# EtherGeiger.net
KiCad netlist of a schematic drawn in EAGLE
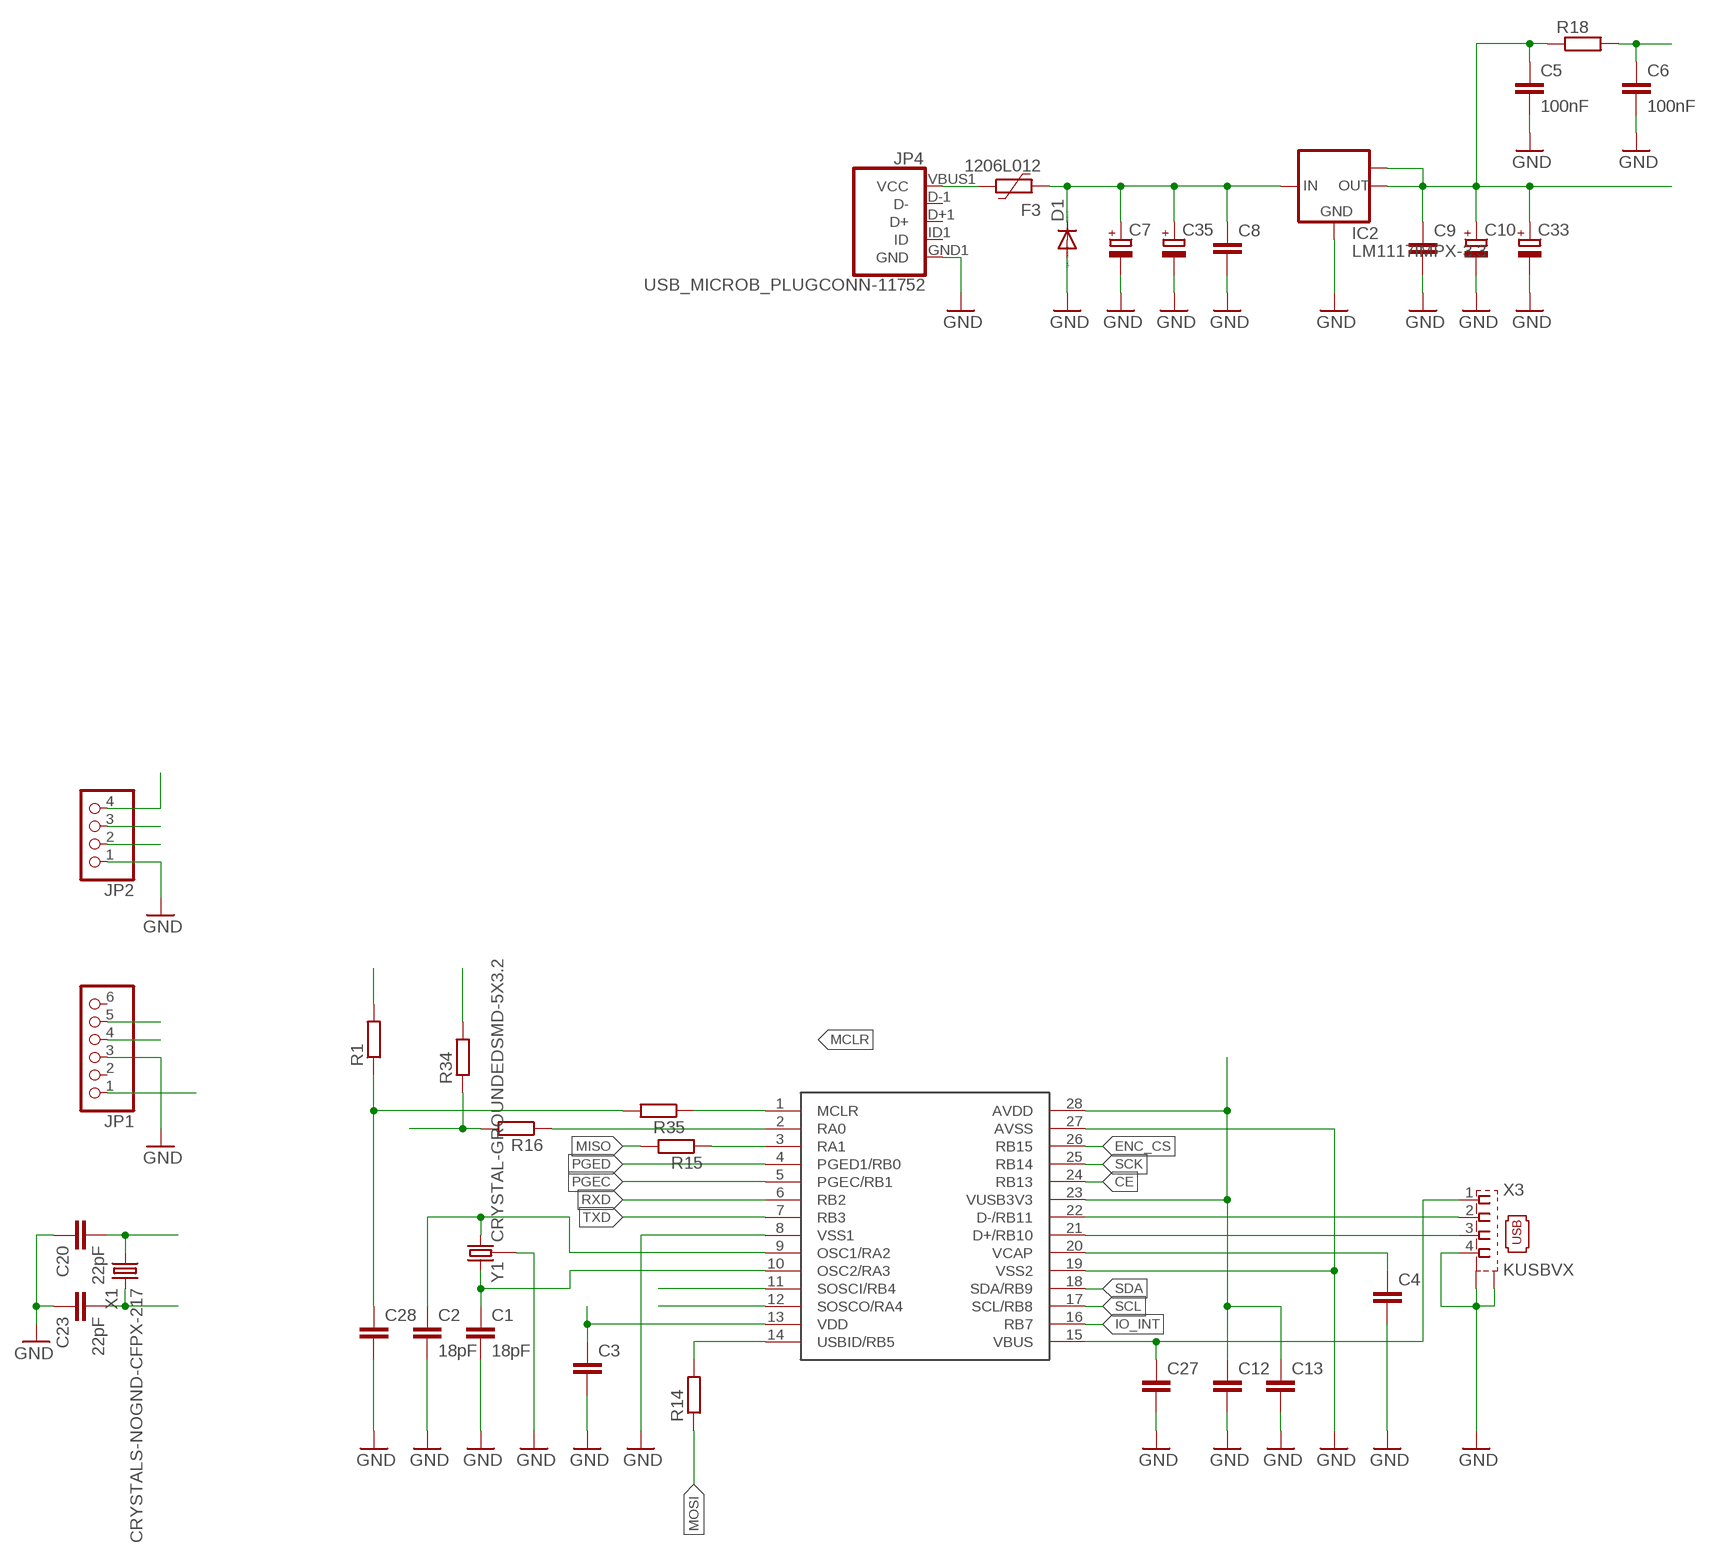
[diagram p0: schematic, sheet 1, part 1 of 3]
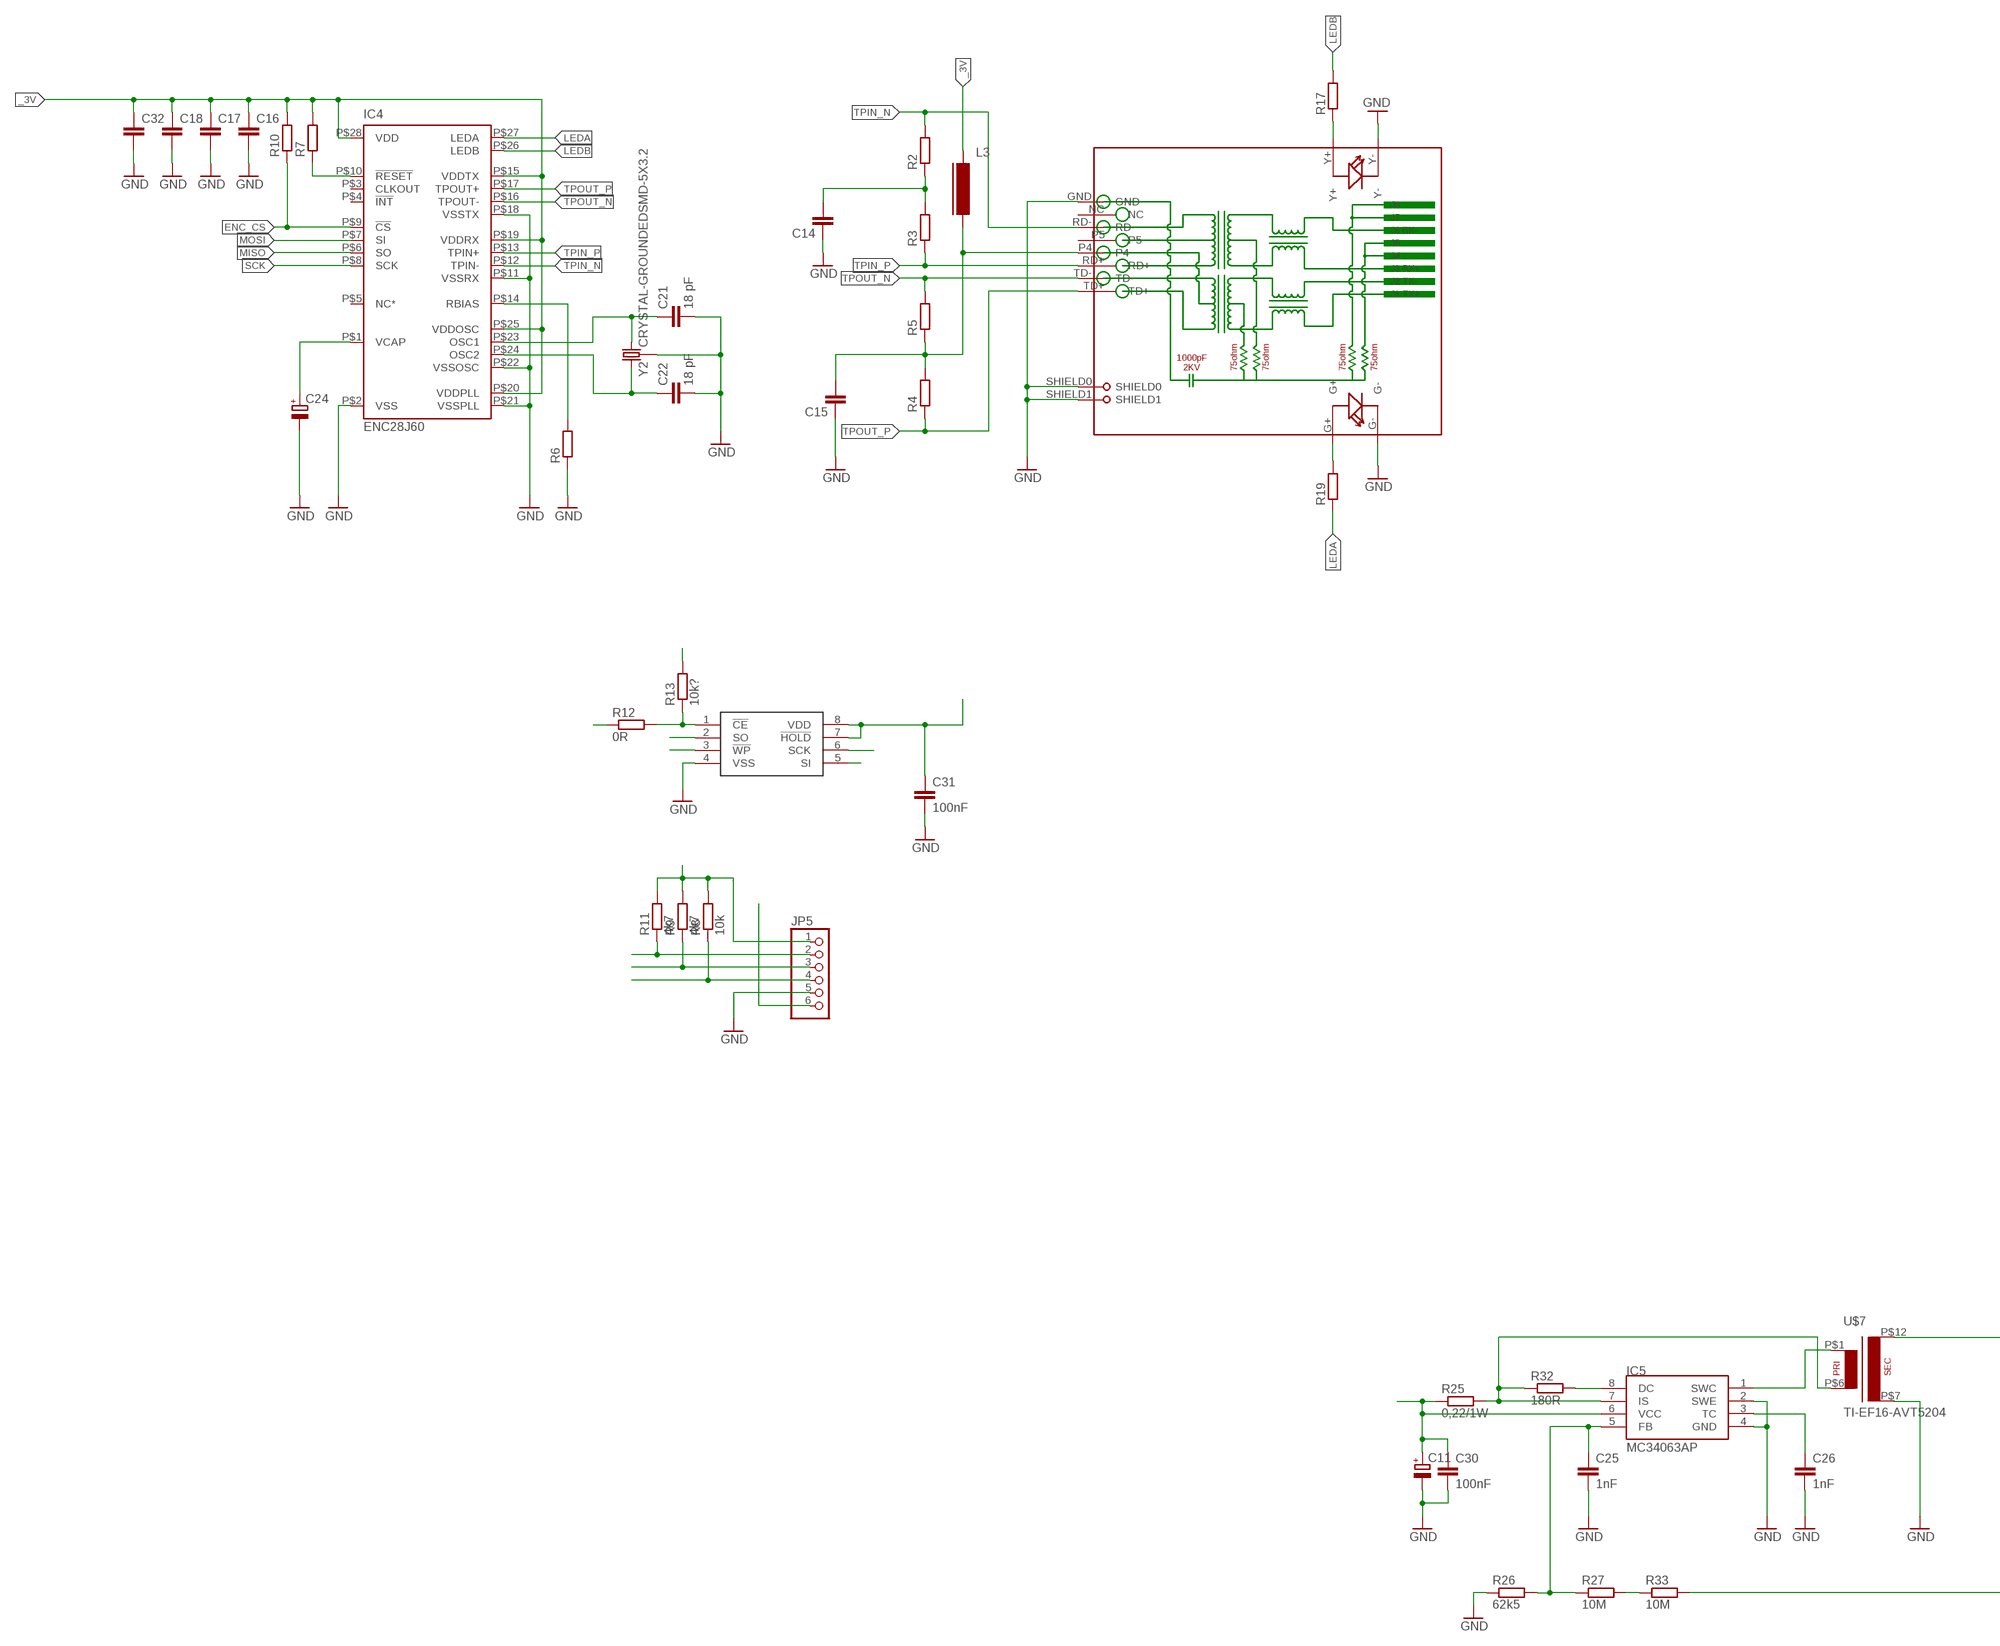
[diagram p1: schematic, sheet 1, part 2 of 3]
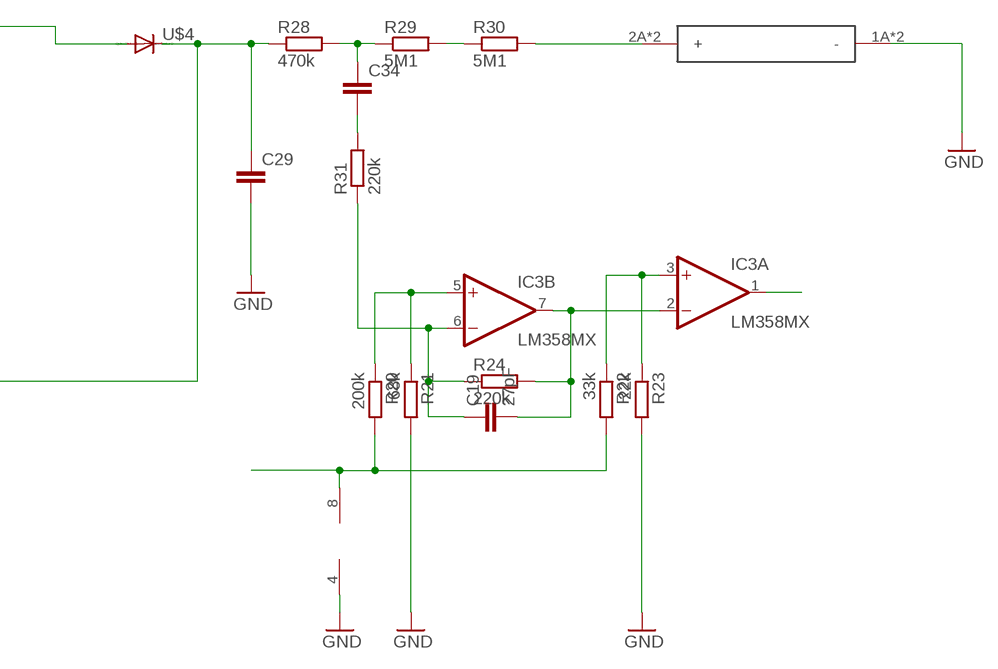
[diagram p2: schematic, sheet 1, part 3 of 3]

(export (version "E")
  (design (tool "Eeschema 10.0.6"))
  (components
    (comp (ref "C1")
      (value "18pF")
      (footprint "eagle-import:C0603")
      (libsource (lib "eagle-import") (part "C-EUC0603"))
    )
    (comp (ref "C2")
      (value "18pF")
      (footprint "eagle-import:C0603")
      (libsource (lib "eagle-import") (part "C-EUC0603"))
    )
    (comp (ref "C3")
      (value "C-EUC0402")
      (footprint "eagle-import:C0402")
      (libsource (lib "eagle-import") (part "C-EUC0402"))
    )
    (comp (ref "C4")
      (value "C-EUC0603")
      (footprint "eagle-import:C0603")
      (libsource (lib "eagle-import") (part "C-EUC0603"))
    )
    (comp (ref "C5")
      (value "100nF")
      (footprint "eagle-import:C0603")
      (libsource (lib "eagle-import") (part "C-EUC0603"))
    )
    (comp (ref "C6")
      (value "100nF")
      (footprint "eagle-import:C0603")
      (libsource (lib "eagle-import") (part "C-EUC0603"))
    )
    (comp (ref "C7")
      (value "CPOL-EUSMCC")
      (footprint "eagle-import:SMC_C")
      (libsource (lib "eagle-import") (part "CPOL-EUSMCC"))
    )
    (comp (ref "C8")
      (value "C-EUC0603")
      (footprint "eagle-import:C0603")
      (libsource (lib "eagle-import") (part "C-EUC0603"))
    )
    (comp (ref "C9")
      (value "C-EUC0603")
      (footprint "eagle-import:C0603")
      (libsource (lib "eagle-import") (part "C-EUC0603"))
    )
    (comp (ref "C10")
      (value "CPOL-EUSMCB")
      (footprint "eagle-import:SMC_B")
      (libsource (lib "eagle-import") (part "CPOL-EUSMCB"))
    )
    (comp (ref "C11")
      (value "CPOL-EUSMCE")
      (footprint "eagle-import:SMC_E")
      (libsource (lib "eagle-import") (part "CPOL-EUSMCE"))
    )
    (comp (ref "C12")
      (value "C-EUC0402")
      (footprint "eagle-import:C0402")
      (libsource (lib "eagle-import") (part "C-EUC0402"))
    )
    (comp (ref "C13")
      (value "C-EUC0603")
      (footprint "eagle-import:C0603")
      (libsource (lib "eagle-import") (part "C-EUC0603"))
    )
    (comp (ref "C14")
      (value "C-EUC0603")
      (footprint "eagle-import:C0603")
      (libsource (lib "eagle-import") (part "C-EUC0603"))
    )
    (comp (ref "C15")
      (value "C-EUC0603")
      (footprint "eagle-import:C0603")
      (libsource (lib "eagle-import") (part "C-EUC0603"))
    )
    (comp (ref "C16")
      (value "C-EUC0402")
      (footprint "eagle-import:C0402")
      (libsource (lib "eagle-import") (part "C-EUC0402"))
    )
    (comp (ref "C17")
      (value "C-EUC0603")
      (footprint "eagle-import:C0603")
      (libsource (lib "eagle-import") (part "C-EUC0603"))
    )
    (comp (ref "C18")
      (value "C-EUC0603")
      (footprint "eagle-import:C0603")
      (libsource (lib "eagle-import") (part "C-EUC0603"))
    )
    (comp (ref "C19")
      (value "27pF")
      (footprint "eagle-import:C0603")
      (libsource (lib "eagle-import") (part "C-EUC0603"))
    )
    (comp (ref "C20")
      (value "22pF")
      (footprint "eagle-import:C0603")
      (libsource (lib "eagle-import") (part "C-EUC0603"))
    )
    (comp (ref "C21")
      (value "18 pF")
      (footprint "eagle-import:C0603")
      (libsource (lib "eagle-import") (part "C-EUC0603"))
    )
    (comp (ref "C22")
      (value "18 pF")
      (footprint "eagle-import:C0603")
      (libsource (lib "eagle-import") (part "C-EUC0603"))
    )
    (comp (ref "C23")
      (value "22pF")
      (footprint "eagle-import:C0603")
      (libsource (lib "eagle-import") (part "C-EUC0603"))
    )
    (comp (ref "C24")
      (value "CPOL-EUSMCA")
      (footprint "eagle-import:SMC_A")
      (libsource (lib "eagle-import") (part "CPOL-EUSMCA"))
    )
    (comp (ref "C25")
      (value "1nF")
      (footprint "eagle-import:C0603")
      (libsource (lib "eagle-import") (part "C-EUC0603"))
    )
    (comp (ref "C26")
      (value "1nF")
      (footprint "eagle-import:C0603")
      (libsource (lib "eagle-import") (part "C-EUC0603"))
    )
    (comp (ref "C27")
      (value "C-EUC0603")
      (footprint "eagle-import:C0603")
      (libsource (lib "eagle-import") (part "C-EUC0603"))
    )
    (comp (ref "C28")
      (value "C-EUC0603")
      (footprint "eagle-import:C0603")
      (libsource (lib "eagle-import") (part "C-EUC0603"))
    )
    (comp (ref "C29")
      (value "C-EU225-113X268")
      (footprint "eagle-import:C225-113X268")
      (libsource (lib "eagle-import") (part "C-EU225-113X268"))
    )
    (comp (ref "C30")
      (value "100nF")
      (footprint "eagle-import:C0603")
      (libsource (lib "eagle-import") (part "C-EUC0603"))
    )
    (comp (ref "C31")
      (value "100nF")
      (footprint "eagle-import:C0603")
      (libsource (lib "eagle-import") (part "C-EUC0603"))
    )
    (comp (ref "C32")
      (value "C-EUC0402")
      (footprint "eagle-import:C0402")
      (libsource (lib "eagle-import") (part "C-EUC0402"))
    )
    (comp (ref "C33")
      (value "CPOL-EUSMCA")
      (footprint "eagle-import:SMC_A")
      (libsource (lib "eagle-import") (part "CPOL-EUSMCA"))
    )
    (comp (ref "C34")
      (value "C-EU050-024X044")
      (footprint "eagle-import:C050-024X044")
      (libsource (lib "eagle-import") (part "C-EU050-024X044"))
    )
    (comp (ref "C35")
      (value "CPOL-EUSMCA")
      (footprint "eagle-import:SMC_A")
      (libsource (lib "eagle-import") (part "CPOL-EUSMCA"))
    )
    (comp (ref "D1")
      (value "DIODE-SMB")
      (footprint "eagle-import:SMB")
      (libsource (lib "eagle-import") (part "DIODE-SMB"))
    )
    (comp (ref "F3")
      (value "1206L012")
      (footprint "eagle-import:1206L")
      (fields (field (name "MF") "Littelfuse"))
      (libsource (lib "eagle-import") (part "?1206L012"))
    )
    (comp (ref "IC2")
      (value "LM1117IMPX-3.3")
      (footprint "eagle-import:SOT223")
      (libsource (lib "eagle-import") (part "LM1117IMPX-3.3"))
    )
    (comp (ref "IC3")
      (value "LM358MX")
      (footprint "eagle-import:SO08")
      (libsource (lib "eagle-import") (part "LM358MX"))
    )
    (comp (ref "IC4")
      (value "ENC28J60")
      (footprint "eagle-import:TSSOP28W")
      (libsource (lib "eagle-import") (part "ENC28J60"))
    )
    (comp (ref "IC5")
      (value "MC34063AP")
      (footprint "eagle-import:DIL08")
      (libsource (lib "eagle-import") (part "MC34063AP"))
    )
    (comp (ref "JP1")
      (value "PINHD-1X6")
      (footprint "eagle-import:1X06")
      (libsource (lib "eagle-import") (part "PINHD-1X6"))
    )
    (comp (ref "JP2")
      (value "PINHD-1X4")
      (footprint "eagle-import:1X04")
      (libsource (lib "eagle-import") (part "PINHD-1X4"))
    )
    (comp (ref "JP4")
      (value "USB_MICROB_PLUGCONN-11752")
      (footprint "eagle-import:USB-B-MICRO-SMD_V03")
      (libsource (lib "eagle-import") (part "USB_MICROB_PLUGCONN-11752"))
    )
    (comp (ref "JP5")
      (value "PINHD-1X6")
      (footprint "eagle-import:1X06")
      (libsource (lib "eagle-import") (part "PINHD-1X6"))
    )
    (comp (ref "L3")
      (value "FERRITE-0805")
      (footprint "eagle-import:FB805")
      (libsource (lib "eagle-import") (part "FERRITE-0805"))
    )
    (comp (ref "R1")
      (value "R-EU_R0603")
      (footprint "eagle-import:R0603")
      (libsource (lib "eagle-import") (part "R-EU_R0603"))
    )
    (comp (ref "R2")
      (value "R-EU_R0603")
      (footprint "eagle-import:R0603")
      (libsource (lib "eagle-import") (part "R-EU_R0603"))
    )
    (comp (ref "R3")
      (value "R-EU_R0603")
      (footprint "eagle-import:R0603")
      (libsource (lib "eagle-import") (part "R-EU_R0603"))
    )
    (comp (ref "R4")
      (value "R-EU_R0603")
      (footprint "eagle-import:R0603")
      (libsource (lib "eagle-import") (part "R-EU_R0603"))
    )
    (comp (ref "R5")
      (value "R-EU_R0603")
      (footprint "eagle-import:R0603")
      (libsource (lib "eagle-import") (part "R-EU_R0603"))
    )
    (comp (ref "R6")
      (value "R-EU_R0805")
      (footprint "eagle-import:R0805")
      (libsource (lib "eagle-import") (part "R-EU_R0805"))
    )
    (comp (ref "R7")
      (value "R-EU_R0603")
      (footprint "eagle-import:R0603")
      (libsource (lib "eagle-import") (part "R-EU_R0603"))
    )
    (comp (ref "R8")
      (value "10k")
      (footprint "eagle-import:R0402")
      (libsource (lib "eagle-import") (part "R-EU_R0402"))
    )
    (comp (ref "R9")
      (value "4k7")
      (footprint "eagle-import:R0402")
      (libsource (lib "eagle-import") (part "R-EU_R0402"))
    )
    (comp (ref "R10")
      (value "R-EU_R0603")
      (footprint "eagle-import:R0603")
      (libsource (lib "eagle-import") (part "R-EU_R0603"))
    )
    (comp (ref "R11")
      (value "4k7")
      (footprint "eagle-import:R0402")
      (libsource (lib "eagle-import") (part "R-EU_R0402"))
    )
    (comp (ref "R12")
      (value "0R")
      (footprint "eagle-import:R0603")
      (libsource (lib "eagle-import") (part "R-EU_R0603"))
    )
    (comp (ref "R13")
      (value "10k?")
      (footprint "eagle-import:R0603")
      (libsource (lib "eagle-import") (part "R-EU_R0603"))
    )
    (comp (ref "R14")
      (value "R-EU_R0603")
      (footprint "eagle-import:R0603")
      (libsource (lib "eagle-import") (part "R-EU_R0603"))
    )
    (comp (ref "R15")
      (value "R-EU_R0603")
      (footprint "eagle-import:R0603")
      (libsource (lib "eagle-import") (part "R-EU_R0603"))
    )
    (comp (ref "R16")
      (value "R-EU_R1206")
      (footprint "eagle-import:R1206")
      (libsource (lib "eagle-import") (part "R-EU_R1206"))
    )
    (comp (ref "R17")
      (value "R-EU_R1206")
      (footprint "eagle-import:R1206")
      (libsource (lib "eagle-import") (part "R-EU_R1206"))
    )
    (comp (ref "R18")
      (value "R-EU_R1206")
      (footprint "eagle-import:R1206")
      (libsource (lib "eagle-import") (part "R-EU_R1206"))
    )
    (comp (ref "R19")
      (value "R-EU_R1206")
      (footprint "eagle-import:R1206")
      (libsource (lib "eagle-import") (part "R-EU_R1206"))
    )
    (comp (ref "R20")
      (value "200k")
      (footprint "eagle-import:R0603")
      (libsource (lib "eagle-import") (part "R-EU_R0603"))
    )
    (comp (ref "R21")
      (value "68k")
      (footprint "eagle-import:R0603")
      (libsource (lib "eagle-import") (part "R-EU_R0603"))
    )
    (comp (ref "R22")
      (value "33k")
      (footprint "eagle-import:R0603")
      (libsource (lib "eagle-import") (part "R-EU_R0603"))
    )
    (comp (ref "R23")
      (value "22k")
      (footprint "eagle-import:R0603")
      (libsource (lib "eagle-import") (part "R-EU_R0603"))
    )
    (comp (ref "R24")
      (value "220k")
      (footprint "eagle-import:R0603")
      (libsource (lib "eagle-import") (part "R-EU_R0603"))
    )
    (comp (ref "R25")
      (value "0,22/1W")
      (footprint "eagle-import:R2010")
      (libsource (lib "eagle-import") (part "R-EU_R2010"))
    )
    (comp (ref "R26")
      (value "62k5")
      (footprint "eagle-import:R1206")
      (libsource (lib "eagle-import") (part "R-EU_R1206"))
    )
    (comp (ref "R27")
      (value "10M")
      (footprint "eagle-import:R2512")
      (libsource (lib "eagle-import") (part "R-EU_R2512"))
    )
    (comp (ref "R28")
      (value "470k")
      (footprint "eagle-import:R2512")
      (libsource (lib "eagle-import") (part "R-EU_R2512"))
    )
    (comp (ref "R29")
      (value "5M1")
      (footprint "eagle-import:R2512")
      (libsource (lib "eagle-import") (part "R-EU_R2512"))
    )
    (comp (ref "R30")
      (value "5M1")
      (footprint "eagle-import:R2512")
      (libsource (lib "eagle-import") (part "R-EU_R2512"))
    )
    (comp (ref "R31")
      (value "220k")
      (footprint "eagle-import:M1206")
      (libsource (lib "eagle-import") (part "R-EU_M1206"))
    )
    (comp (ref "R32")
      (value "180R")
      (footprint "eagle-import:R0805")
      (libsource (lib "eagle-import") (part "R-EU_R0805"))
    )
    (comp (ref "R33")
      (value "10M")
      (footprint "eagle-import:R2512")
      (libsource (lib "eagle-import") (part "R-EU_R2512"))
    )
    (comp (ref "R34")
      (value "R-EU_R0603")
      (footprint "eagle-import:R0603")
      (libsource (lib "eagle-import") (part "R-EU_R0603"))
    )
    (comp (ref "R35")
      (value "R-EU_R0603")
      (footprint "eagle-import:R0603")
      (libsource (lib "eagle-import") (part "R-EU_R0603"))
    )
    (comp (ref "RJ1")
      (value "HR911105A")
      (footprint "eagle-import:HR911105A")
      (libsource (lib "eagle-import") (part "HR911105A"))
    )
    (comp (ref "U$1")
      (value "PIC32MX250F128B2")
      (footprint "eagle-import:SSOP28")
      (libsource (lib "eagle-import") (part "PIC32MX250F128B2"))
    )
    (comp (ref "U$2")
      (value "SST25VF016BSO8M")
      (footprint "eagle-import:SO-08M")
      (libsource (lib "eagle-import") (part "SST25VF016BSO8M"))
    )
    (comp (ref "U$4")
      (value "DIODE-MELF-MLL41")
      (footprint "eagle-import:MELF-MLL41")
      (libsource (lib "eagle-import") (part "DIODE-MELF-MLL41"))
    )
    (comp (ref "U$5")
      (value "STS5")
      (footprint "eagle-import:GEIGERTUBE")
      (libsource (lib "eagle-import") (part "STS5"))
    )
    (comp (ref "U$7")
      (value "TI-EF16-AVT5204")
      (footprint "eagle-import:EF16-K-H-12P-12,5")
      (libsource (lib "eagle-import") (part "TI-EF16-AVT5204"))
    )
    (comp (ref "X1")
      (value "CRYSTALS-NOGND-CFPX-217")
      (footprint "eagle-import:3.2X1.5-2-PAD")
      (libsource (lib "eagle-import") (part "CRYSTALS-NOGND-CFPX-217"))
    )
    (comp (ref "X3")
      (value "KUSBVX")
      (footprint "eagle-import:KUSBVX")
      (libsource (lib "eagle-import") (part "KUSBVX"))
    )
    (comp (ref "Y1")
      (value "CRYSTAL-GROUNDEDSMD-5X3.2")
      (footprint "eagle-import:CRYSTAL-SMD-5X3.2-4PAD")
      (libsource (lib "eagle-import") (part "CRYSTAL-GROUNDEDSMD-5X3.2"))
    )
    (comp (ref "Y2")
      (value "CRYSTAL-GROUNDEDSMD-5X3.2")
      (footprint "eagle-import:CRYSTAL-SMD-5X3.2-4PAD")
      (libsource (lib "eagle-import") (part "CRYSTAL-GROUNDEDSMD-5X3.2"))
    )
  )
  (nets
    (net (code "1") (name "/A_3V") (class "Default")
      (node (ref "C6") (pin "1") (pinfunction "1_1") (pintype "passive"))
      (node (ref "IC3") (pin "8") (pinfunction "V+_8") (pintype "power_in"))
      (node (ref "R18") (pin "2") (pinfunction "2_2") (pintype "passive"))
      (node (ref "R20") (pin "2") (pinfunction "2_2") (pintype "passive"))
      (node (ref "R22") (pin "2") (pinfunction "2_2") (pintype "passive"))
    )
    (net (code "2") (name "/CPM") (class "Default")
      (node (ref "IC3") (pin "1") (pinfunction "OUT_1") (pintype "output"))
      (node (ref "R16") (pin "2") (pinfunction "2_2") (pintype "passive"))
      (node (ref "R34") (pin "1") (pinfunction "1_1") (pintype "passive"))
    )
    (net (code "3") (name "/SOSCI") (class "Default")
      (node (ref "C20") (pin "2") (pinfunction "2_2") (pintype "passive"))
      (node (ref "U$1") (pin "11") (pinfunction "SOSCI/RB4_11") (pintype "bidirectional"))
      (node (ref "X1") (pin "1") (pinfunction "1_1") (pintype "passive"))
    )
    (net (code "4") (name "/SOSCO") (class "Default")
      (node (ref "C23") (pin "2") (pinfunction "2_2") (pintype "passive"))
      (node (ref "U$1") (pin "12") (pinfunction "SOSCO/RA4_12") (pintype "bidirectional"))
      (node (ref "X1") (pin "2") (pinfunction "2_2") (pintype "passive"))
    )
    (net (code "5") (name "/VBUS") (class "Default")
      (node (ref "C11") (pin "+") (pinfunction "+_+") (pintype "passive"))
      (node (ref "C27") (pin "1") (pinfunction "1_1") (pintype "passive"))
      (node (ref "C30") (pin "1") (pinfunction "1_1") (pintype "passive"))
      (node (ref "C35") (pin "+") (pinfunction "+_+") (pintype "passive"))
      (node (ref "C7") (pin "+") (pinfunction "+_+") (pintype "passive"))
      (node (ref "C8") (pin "1") (pinfunction "1_1") (pintype "passive"))
      (node (ref "D1") (pin "C") (pinfunction "C_C") (pintype "passive"))
      (node (ref "F3") (pin "2") (pinfunction "2_2") (pintype "passive"))
      (node (ref "IC2") (pin "3") (pinfunction "IN_3") (pintype "input"))
      (node (ref "IC5") (pin "6") (pinfunction "VCC_6") (pintype "passive"))
      (node (ref "JP5") (pin "6") (pinfunction "6_6") (pintype "passive"))
      (node (ref "R25") (pin "1") (pinfunction "1_1") (pintype "passive"))
      (node (ref "U$1") (pin "15") (pinfunction "VBUS_15") (pintype "bidirectional"))
      (node (ref "X3") (pin "1") (pinfunction "1_1") (pintype "passive"))
    )
    (net (code "6") (name "CE") (class "Default")
      (node (ref "R12") (pin "1") (pinfunction "1_1") (pintype "passive"))
      (node (ref "U$1") (pin "24") (pinfunction "RB13_24") (pintype "bidirectional"))
    )
    (net (code "7") (name "ENC_CS") (class "Default")
      (node (ref "IC4") (pin "P$9") (pinfunction "~{CS}_P$9") (pintype "input"))
      (node (ref "R10") (pin "1") (pinfunction "1_1") (pintype "passive"))
      (node (ref "U$1") (pin "26") (pinfunction "RB15_26") (pintype "bidirectional"))
    )
    (net (code "8") (name "GND") (class "Default")
      (node (ref "C1") (pin "2") (pinfunction "2_2") (pintype "passive"))
      (node (ref "C10") (pin "-") (pinfunction "-_-") (pintype "passive"))
      (node (ref "C11") (pin "-") (pinfunction "-_-") (pintype "passive"))
      (node (ref "C12") (pin "2") (pinfunction "2_2") (pintype "passive"))
      (node (ref "C13") (pin "2") (pinfunction "2_2") (pintype "passive"))
      (node (ref "C14") (pin "1") (pinfunction "1_1") (pintype "passive"))
      (node (ref "C15") (pin "1") (pinfunction "1_1") (pintype "passive"))
      (node (ref "C16") (pin "2") (pinfunction "2_2") (pintype "passive"))
      (node (ref "C17") (pin "2") (pinfunction "2_2") (pintype "passive"))
      (node (ref "C18") (pin "2") (pinfunction "2_2") (pintype "passive"))
      (node (ref "C2") (pin "2") (pinfunction "2_2") (pintype "passive"))
      (node (ref "C20") (pin "1") (pinfunction "1_1") (pintype "passive"))
      (node (ref "C21") (pin "2") (pinfunction "2_2") (pintype "passive"))
      (node (ref "C22") (pin "2") (pinfunction "2_2") (pintype "passive"))
      (node (ref "C23") (pin "1") (pinfunction "1_1") (pintype "passive"))
      (node (ref "C24") (pin "-") (pinfunction "-_-") (pintype "passive"))
      (node (ref "C25") (pin "2") (pinfunction "2_2") (pintype "passive"))
      (node (ref "C26") (pin "2") (pinfunction "2_2") (pintype "passive"))
      (node (ref "C27") (pin "2") (pinfunction "2_2") (pintype "passive"))
      (node (ref "C28") (pin "2") (pinfunction "2_2") (pintype "passive"))
      (node (ref "C29") (pin "2") (pinfunction "2_2") (pintype "passive"))
      (node (ref "C3") (pin "2") (pinfunction "2_2") (pintype "passive"))
      (node (ref "C30") (pin "2") (pinfunction "2_2") (pintype "passive"))
      (node (ref "C31") (pin "2") (pinfunction "2_2") (pintype "passive"))
      (node (ref "C32") (pin "2") (pinfunction "2_2") (pintype "passive"))
      (node (ref "C33") (pin "-") (pinfunction "-_-") (pintype "passive"))
      (node (ref "C35") (pin "-") (pinfunction "-_-") (pintype "passive"))
      (node (ref "C4") (pin "2") (pinfunction "2_2") (pintype "passive"))
      (node (ref "C5") (pin "2") (pinfunction "2_2") (pintype "passive"))
      (node (ref "C6") (pin "2") (pinfunction "2_2") (pintype "passive"))
      (node (ref "C7") (pin "-") (pinfunction "-_-") (pintype "passive"))
      (node (ref "C8") (pin "2") (pinfunction "2_2") (pintype "passive"))
      (node (ref "C9") (pin "2") (pinfunction "2_2") (pintype "passive"))
      (node (ref "D1") (pin "A") (pinfunction "A_A") (pintype "passive"))
      (node (ref "IC2") (pin "1") (pinfunction "GND_1") (pintype "input"))
      (node (ref "IC3") (pin "4") (pinfunction "V-_4") (pintype "power_in"))
      (node (ref "IC4") (pin "P$11") (pinfunction "VSSRX_P$11") (pintype "input"))
      (node (ref "IC4") (pin "P$18") (pinfunction "VSSTX_P$18") (pintype "input"))
      (node (ref "IC4") (pin "P$2") (pinfunction "VSS_P$2") (pintype "input"))
      (node (ref "IC4") (pin "P$21") (pinfunction "VSSPLL_P$21") (pintype "input"))
      (node (ref "IC4") (pin "P$22") (pinfunction "VSSOSC_P$22") (pintype "input"))
      (node (ref "IC5") (pin "2") (pinfunction "SWE_2") (pintype "passive"))
      (node (ref "IC5") (pin "4") (pinfunction "GND_4") (pintype "passive"))
      (node (ref "JP1") (pin "3") (pinfunction "3_3") (pintype "passive"))
      (node (ref "JP2") (pin "1") (pinfunction "1_1") (pintype "passive"))
      (node (ref "JP4") (pin "GND1") (pinfunction "GND_GND1") (pintype "bidirectional"))
      (node (ref "JP5") (pin "5") (pinfunction "5_5") (pintype "passive"))
      (node (ref "R21") (pin "2") (pinfunction "2_2") (pintype "passive"))
      (node (ref "R23") (pin "2") (pinfunction "2_2") (pintype "passive"))
      (node (ref "R26") (pin "1") (pinfunction "1_1") (pintype "passive"))
      (node (ref "R6") (pin "1") (pinfunction "1_1") (pintype "passive"))
      (node (ref "RJ1") (pin "G-") (pinfunction "G-_G-") (pintype "bidirectional"))
      (node (ref "RJ1") (pin "GND") (pinfunction "GND_GND") (pintype "bidirectional"))
      (node (ref "RJ1") (pin "SHIELD0") (pinfunction "SHIELD0_SHIELD0") (pintype "bidirectional"))
      (node (ref "RJ1") (pin "SHIELD1") (pinfunction "SHIELD1_SHIELD1") (pintype "bidirectional"))
      (node (ref "RJ1") (pin "Y-") (pinfunction "Y-_Y-") (pintype "bidirectional"))
      (node (ref "U$1") (pin "19") (pinfunction "VSS2_19") (pintype "bidirectional"))
      (node (ref "U$1") (pin "27") (pinfunction "AVSS_27") (pintype "bidirectional"))
      (node (ref "U$1") (pin "8") (pinfunction "VSS1_8") (pintype "bidirectional"))
      (node (ref "U$2") (pin "4") (pinfunction "VSS_4") (pintype "bidirectional"))
      (node (ref "U$5") (pin "1A") (pinfunction "-_1A") (pintype "bidirectional"))
      (node (ref "U$5") (pin "1B") (pinfunction "-_1B") (pintype "bidirectional"))
      (node (ref "U$7") (pin "P$7") (pinfunction "P7_P$7") (pintype "passive"))
      (node (ref "X3") (pin "4") (pinfunction "4_4") (pintype "passive"))
      (node (ref "X3") (pin "M1") (pinfunction "S1_M1") (pintype "passive"))
      (node (ref "X3") (pin "M2") (pinfunction "S2_M2") (pintype "passive"))
      (node (ref "Y1") (pin "2") (pinfunction "3_2") (pintype "passive"))
      (node (ref "Y1") (pin "4") (pinfunction "3_4") (pintype "passive"))
      (node (ref "Y2") (pin "2") (pinfunction "3_2") (pintype "passive"))
      (node (ref "Y2") (pin "4") (pinfunction "3_4") (pintype "passive"))
    )
    (net (code "9") (name "IO_INT") (class "Default")
      (node (ref "JP5") (pin "4") (pinfunction "4_4") (pintype "passive"))
      (node (ref "R8") (pin "1") (pinfunction "1_1") (pintype "passive"))
      (node (ref "U$1") (pin "16") (pinfunction "RB7_16") (pintype "bidirectional"))
    )
    (net (code "10") (name "LEDA") (class "Default")
      (node (ref "IC4") (pin "P$27") (pinfunction "LEDA_P$27") (pintype "output"))
      (node (ref "R19") (pin "1") (pinfunction "1_1") (pintype "passive"))
    )
    (net (code "11") (name "LEDB") (class "Default")
      (node (ref "IC4") (pin "P$26") (pinfunction "LEDB_P$26") (pintype "output"))
      (node (ref "R17") (pin "2") (pinfunction "2_2") (pintype "passive"))
    )
    (net (code "12") (name "MCLR") (class "Default")
      (node (ref "JP1") (pin "1") (pinfunction "1_1") (pintype "passive"))
      (node (ref "R35") (pin "1") (pinfunction "1_1") (pintype "passive"))
      (node (ref "U$1") (pin "1") (pinfunction "MCLR_1") (pintype "bidirectional"))
    )
    (net (code "13") (name "MISO") (class "Default")
      (node (ref "IC4") (pin "P$6") (pinfunction "SO_P$6") (pintype "output"))
      (node (ref "R15") (pin "2") (pinfunction "2_2") (pintype "passive"))
      (node (ref "U$2") (pin "2") (pinfunction "SO_2") (pintype "bidirectional"))
    )
    (net (code "14") (name "MOSI") (class "Default")
      (node (ref "IC4") (pin "P$7") (pinfunction "SI_P$7") (pintype "input"))
      (node (ref "R14") (pin "1") (pinfunction "1_1") (pintype "passive"))
      (node (ref "U$2") (pin "5") (pinfunction "SI_5") (pintype "bidirectional"))
    )
    (net (code "15") (name "Net-(C14-Pad2)") (class "Default")
      (node (ref "C14") (pin "2") (pinfunction "2_2") (pintype "passive"))
      (node (ref "R2") (pin "1") (pinfunction "1_1") (pintype "passive"))
      (node (ref "R3") (pin "2") (pinfunction "2_2") (pintype "passive"))
    )
    (net (code "16") (name "Net-(C15-Pad2)") (class "Default")
      (node (ref "C15") (pin "2") (pinfunction "2_2") (pintype "passive"))
      (node (ref "L3") (pin "2") (pinfunction "2_2") (pintype "passive"))
      (node (ref "R4") (pin "2") (pinfunction "2_2") (pintype "passive"))
      (node (ref "R5") (pin "1") (pinfunction "1_1") (pintype "passive"))
      (node (ref "RJ1") (pin "P4") (pinfunction "P4_P4") (pintype "bidirectional"))
    )
    (net (code "17") (name "Net-(C28-Pad1)") (class "Default")
      (node (ref "C28") (pin "1") (pinfunction "1_1") (pintype "passive"))
      (node (ref "R1") (pin "1") (pinfunction "1_1") (pintype "passive"))
      (node (ref "R35") (pin "2") (pinfunction "2_2") (pintype "passive"))
    )
    (net (code "18") (name "Net-(C29-Pad1)") (class "Default")
      (node (ref "C29") (pin "1") (pinfunction "1_1") (pintype "passive"))
      (node (ref "R28") (pin "1") (pinfunction "1_1") (pintype "passive"))
      (node (ref "R33") (pin "2") (pinfunction "2_2") (pintype "passive"))
      (node (ref "U$4") (pin "C") (pinfunction "C_C") (pintype "passive"))
    )
    (net (code "19") (name "Net-(C34-Pad1)") (class "Default")
      (node (ref "C34") (pin "1") (pinfunction "1_1") (pintype "passive"))
      (node (ref "R28") (pin "2") (pinfunction "2_2") (pintype "passive"))
      (node (ref "R29") (pin "1") (pinfunction "1_1") (pintype "passive"))
    )
    (net (code "20") (name "Net-(C34-Pad2)") (class "Default")
      (node (ref "C34") (pin "2") (pinfunction "2_2") (pintype "passive"))
      (node (ref "R31") (pin "2") (pinfunction "2_2") (pintype "passive"))
    )
    (net (code "21") (name "Net-(IC3A-+IN)") (class "Default")
      (node (ref "IC3") (pin "3") (pinfunction "+IN_3") (pintype "input"))
      (node (ref "R22") (pin "1") (pinfunction "1_1") (pintype "passive"))
      (node (ref "R23") (pin "1") (pinfunction "1_1") (pintype "passive"))
    )
    (net (code "22") (name "Net-(IC3A--IN)") (class "Default")
      (node (ref "C19") (pin "2") (pinfunction "2_2") (pintype "passive"))
      (node (ref "IC3") (pin "2") (pinfunction "-IN_2") (pintype "input"))
      (node (ref "IC3") (pin "7") (pinfunction "OUT_7") (pintype "output"))
      (node (ref "R24") (pin "2") (pinfunction "2_2") (pintype "passive"))
    )
    (net (code "23") (name "Net-(IC3B-+IN)") (class "Default")
      (node (ref "IC3") (pin "5") (pinfunction "+IN_5") (pintype "input"))
      (node (ref "R20") (pin "1") (pinfunction "1_1") (pintype "passive"))
      (node (ref "R21") (pin "1") (pinfunction "1_1") (pintype "passive"))
    )
    (net (code "24") (name "Net-(IC3B--IN)") (class "Default")
      (node (ref "C19") (pin "1") (pinfunction "1_1") (pintype "passive"))
      (node (ref "IC3") (pin "6") (pinfunction "-IN_6") (pintype "input"))
      (node (ref "R24") (pin "1") (pinfunction "1_1") (pintype "passive"))
      (node (ref "R31") (pin "1") (pinfunction "1_1") (pintype "passive"))
    )
    (net (code "25") (name "Net-(IC4-OSC1)") (class "Default")
      (node (ref "C21") (pin "1") (pinfunction "1_1") (pintype "passive"))
      (node (ref "IC4") (pin "P$23") (pinfunction "OSC1_P$23") (pintype "input"))
      (node (ref "Y2") (pin "1") (pinfunction "2_1") (pintype "passive"))
    )
    (net (code "26") (name "Net-(IC4-OSC2)") (class "Default")
      (node (ref "C22") (pin "1") (pinfunction "1_1") (pintype "passive"))
      (node (ref "IC4") (pin "P$24") (pinfunction "OSC2_P$24") (pintype "output"))
      (node (ref "Y2") (pin "3") (pinfunction "1_3") (pintype "passive"))
    )
    (net (code "27") (name "Net-(IC4-RBIAS)") (class "Default")
      (node (ref "IC4") (pin "P$14") (pinfunction "RBIAS_P$14") (pintype "input"))
      (node (ref "R6") (pin "2") (pinfunction "2_2") (pintype "passive"))
    )
    (net (code "28") (name "Net-(IC4-VCAP)") (class "Default")
      (node (ref "C24") (pin "+") (pinfunction "+_+") (pintype "passive"))
      (node (ref "IC4") (pin "P$1") (pinfunction "VCAP_P$1") (pintype "input"))
    )
    (net (code "29") (name "Net-(IC4-~{RESET})") (class "Default")
      (node (ref "IC4") (pin "P$10") (pinfunction "~{RESET}_P$10") (pintype "input"))
      (node (ref "R7") (pin "1") (pinfunction "1_1") (pintype "passive"))
    )
    (net (code "30") (name "Net-(IC5-DC)") (class "Default")
      (node (ref "IC5") (pin "8") (pinfunction "DC_8") (pintype "passive"))
      (node (ref "R32") (pin "2") (pinfunction "2_2") (pintype "passive"))
    )
    (net (code "31") (name "Net-(IC5-FB)") (class "Default")
      (node (ref "C25") (pin "1") (pinfunction "1_1") (pintype "passive"))
      (node (ref "IC5") (pin "5") (pinfunction "FB_5") (pintype "passive"))
      (node (ref "R26") (pin "2") (pinfunction "2_2") (pintype "passive"))
      (node (ref "R27") (pin "1") (pinfunction "1_1") (pintype "passive"))
    )
    (net (code "32") (name "Net-(IC5-IS)") (class "Default")
      (node (ref "IC5") (pin "7") (pinfunction "IS_7") (pintype "passive"))
      (node (ref "R25") (pin "2") (pinfunction "2_2") (pintype "passive"))
      (node (ref "R32") (pin "1") (pinfunction "1_1") (pintype "passive"))
      (node (ref "U$7") (pin "P$6") (pinfunction "P6_P$6") (pintype "passive"))
    )
    (net (code "33") (name "Net-(IC5-SWC)") (class "Default")
      (node (ref "IC5") (pin "1") (pinfunction "SWC_1") (pintype "passive"))
      (node (ref "U$7") (pin "P$1") (pinfunction "P1_P$1") (pintype "passive"))
    )
    (net (code "34") (name "Net-(IC5-TC)") (class "Default")
      (node (ref "C26") (pin "1") (pinfunction "1_1") (pintype "passive"))
      (node (ref "IC5") (pin "3") (pinfunction "TC_3") (pintype "passive"))
    )
    (net (code "35") (name "Net-(JP4-VCC)") (class "Default")
      (node (ref "F3") (pin "1") (pinfunction "1_1") (pintype "passive"))
      (node (ref "JP4") (pin "VBUS1") (pinfunction "VCC_VBUS1") (pintype "bidirectional"))
    )
    (net (code "36") (name "Net-(R17-Pad1)") (class "Default")
      (node (ref "R17") (pin "1") (pinfunction "1_1") (pintype "passive"))
      (node (ref "RJ1") (pin "Y+") (pinfunction "Y+_Y+") (pintype "bidirectional"))
    )
    (net (code "37") (name "Net-(R19-Pad2)") (class "Default")
      (node (ref "R19") (pin "2") (pinfunction "2_2") (pintype "passive"))
      (node (ref "RJ1") (pin "G+") (pinfunction "G+_G+") (pintype "bidirectional"))
    )
    (net (code "38") (name "Net-(R27-Pad2)") (class "Default")
      (node (ref "R27") (pin "2") (pinfunction "2_2") (pintype "passive"))
      (node (ref "R33") (pin "1") (pinfunction "1_1") (pintype "passive"))
    )
    (net (code "39") (name "Net-(R29-Pad2)") (class "Default")
      (node (ref "R29") (pin "2") (pinfunction "2_2") (pintype "passive"))
      (node (ref "R30") (pin "1") (pinfunction "1_1") (pintype "passive"))
    )
    (net (code "40") (name "Net-(R30-Pad2)") (class "Default")
      (node (ref "R30") (pin "2") (pinfunction "2_2") (pintype "passive"))
      (node (ref "U$5") (pin "2A") (pinfunction "+_2A") (pintype "bidirectional"))
      (node (ref "U$5") (pin "2B") (pinfunction "+_2B") (pintype "bidirectional"))
    )
    (net (code "41") (name "Net-(U$1-D+{slash}RB10)") (class "Default")
      (node (ref "U$1") (pin "21") (pinfunction "D+/RB10_21") (pintype "bidirectional"))
      (node (ref "X3") (pin "3") (pinfunction "3_3") (pintype "passive"))
    )
    (net (code "42") (name "Net-(U$1-D-{slash}RB11)") (class "Default")
      (node (ref "U$1") (pin "22") (pinfunction "D-/RB11_22") (pintype "bidirectional"))
      (node (ref "X3") (pin "2") (pinfunction "2_2") (pintype "passive"))
    )
    (net (code "43") (name "Net-(U$1-OSC1{slash}RA2)") (class "Default")
      (node (ref "C2") (pin "1") (pinfunction "1_1") (pintype "passive"))
      (node (ref "U$1") (pin "9") (pinfunction "OSC1/RA2_9") (pintype "bidirectional"))
      (node (ref "Y1") (pin "1") (pinfunction "2_1") (pintype "passive"))
    )
    (net (code "44") (name "Net-(U$1-OSC2{slash}RA3)") (class "Default")
      (node (ref "C1") (pin "1") (pinfunction "1_1") (pintype "passive"))
      (node (ref "U$1") (pin "10") (pinfunction "OSC2/RA3_10") (pintype "bidirectional"))
      (node (ref "Y1") (pin "3") (pinfunction "1_3") (pintype "passive"))
    )
    (net (code "45") (name "Net-(U$1-RA0)") (class "Default")
      (node (ref "R16") (pin "1") (pinfunction "1_1") (pintype "passive"))
      (node (ref "U$1") (pin "2") (pinfunction "RA0_2") (pintype "bidirectional"))
    )
    (net (code "46") (name "Net-(U$1-RA1)") (class "Default")
      (node (ref "R15") (pin "1") (pinfunction "1_1") (pintype "passive"))
      (node (ref "U$1") (pin "3") (pinfunction "RA1_3") (pintype "bidirectional"))
    )
    (net (code "47") (name "Net-(U$1-USBID{slash}RB5)") (class "Default")
      (node (ref "R14") (pin "2") (pinfunction "2_2") (pintype "passive"))
      (node (ref "U$1") (pin "14") (pinfunction "USBID/RB5_14") (pintype "bidirectional"))
    )
    (net (code "48") (name "Net-(U$1-VCAP)") (class "Default")
      (node (ref "C4") (pin "1") (pinfunction "1_1") (pintype "passive"))
      (node (ref "U$1") (pin "20") (pinfunction "VCAP_20") (pintype "bidirectional"))
    )
    (net (code "49") (name "Net-(U$2-~{CE})") (class "Default")
      (node (ref "R12") (pin "2") (pinfunction "2_2") (pintype "passive"))
      (node (ref "R13") (pin "1") (pinfunction "1_1") (pintype "passive"))
      (node (ref "U$2") (pin "1") (pinfunction "~{CE}_1") (pintype "bidirectional"))
    )
    (net (code "50") (name "Net-(U$7-P12)") (class "Default")
      (node (ref "U$4") (pin "A") (pinfunction "A_A") (pintype "passive"))
      (node (ref "U$7") (pin "P$12") (pinfunction "P12_P$12") (pintype "passive"))
    )
    (net (code "51") (name "PGEC") (class "Default")
      (node (ref "JP1") (pin "5") (pinfunction "5_5") (pintype "passive"))
      (node (ref "U$1") (pin "5") (pinfunction "PGEC/RB1_5") (pintype "bidirectional"))
    )
    (net (code "52") (name "PGED") (class "Default")
      (node (ref "JP1") (pin "4") (pinfunction "4_4") (pintype "passive"))
      (node (ref "U$1") (pin "4") (pinfunction "PGED1/RB0_4") (pintype "bidirectional"))
    )
    (net (code "53") (name "RXD") (class "Default")
      (node (ref "JP2") (pin "3") (pinfunction "3_3") (pintype "passive"))
      (node (ref "U$1") (pin "6") (pinfunction "RB2_6") (pintype "bidirectional"))
    )
    (net (code "54") (name "SCK") (class "Default")
      (node (ref "IC4") (pin "P$8") (pinfunction "SCK_P$8") (pintype "input"))
      (node (ref "U$1") (pin "25") (pinfunction "RB14_25") (pintype "bidirectional"))
      (node (ref "U$2") (pin "6") (pinfunction "SCK_6") (pintype "bidirectional"))
    )
    (net (code "55") (name "SCL") (class "Default")
      (node (ref "JP5") (pin "3") (pinfunction "3_3") (pintype "passive"))
      (node (ref "R9") (pin "1") (pinfunction "1_1") (pintype "passive"))
      (node (ref "U$1") (pin "17") (pinfunction "SCL/RB8_17") (pintype "bidirectional"))
    )
    (net (code "56") (name "SDA") (class "Default")
      (node (ref "JP5") (pin "2") (pinfunction "2_2") (pintype "passive"))
      (node (ref "R11") (pin "1") (pinfunction "1_1") (pintype "passive"))
      (node (ref "U$1") (pin "18") (pinfunction "SDA/RB9_18") (pintype "bidirectional"))
    )
    (net (code "57") (name "TPIN_N") (class "Default")
      (node (ref "IC4") (pin "P$12") (pinfunction "TPIN-_P$12") (pintype "input"))
      (node (ref "R2") (pin "2") (pinfunction "2_2") (pintype "passive"))
      (node (ref "RJ1") (pin "RD-") (pinfunction "RD-_RD-") (pintype "bidirectional"))
    )
    (net (code "58") (name "TPIN_P") (class "Default")
      (node (ref "IC4") (pin "P$13") (pinfunction "TPIN+_P$13") (pintype "input"))
      (node (ref "R3") (pin "1") (pinfunction "1_1") (pintype "passive"))
      (node (ref "RJ1") (pin "RD+") (pinfunction "RD+_RD+") (pintype "bidirectional"))
    )
    (net (code "59") (name "TPOUT_N") (class "Default")
      (node (ref "IC4") (pin "P$16") (pinfunction "TPOUT-_P$16") (pintype "output"))
      (node (ref "R5") (pin "2") (pinfunction "2_2") (pintype "passive"))
      (node (ref "RJ1") (pin "TD-") (pinfunction "TD-_TD-") (pintype "bidirectional"))
    )
    (net (code "60") (name "TPOUT_P") (class "Default")
      (node (ref "IC4") (pin "P$17") (pinfunction "TPOUT+_P$17") (pintype "output"))
      (node (ref "R4") (pin "1") (pinfunction "1_1") (pintype "passive"))
      (node (ref "RJ1") (pin "TD+") (pinfunction "TD+_TD+") (pintype "bidirectional"))
    )
    (net (code "61") (name "TXD") (class "Default")
      (node (ref "JP2") (pin "2") (pinfunction "2_2") (pintype "passive"))
      (node (ref "U$1") (pin "7") (pinfunction "RB3_7") (pintype "bidirectional"))
    )
    (net (code "62") (name "_3V") (class "Default")
      (node (ref "C10") (pin "+") (pinfunction "+_+") (pintype "passive"))
      (node (ref "C12") (pin "1") (pinfunction "1_1") (pintype "passive"))
      (node (ref "C13") (pin "1") (pinfunction "1_1") (pintype "passive"))
      (node (ref "C16") (pin "1") (pinfunction "1_1") (pintype "passive"))
      (node (ref "C17") (pin "1") (pinfunction "1_1") (pintype "passive"))
      (node (ref "C18") (pin "1") (pinfunction "1_1") (pintype "passive"))
      (node (ref "C3") (pin "1") (pinfunction "1_1") (pintype "passive"))
      (node (ref "C31") (pin "1") (pinfunction "1_1") (pintype "passive"))
      (node (ref "C32") (pin "1") (pinfunction "1_1") (pintype "passive"))
      (node (ref "C33") (pin "+") (pinfunction "+_+") (pintype "passive"))
      (node (ref "C5") (pin "1") (pinfunction "1_1") (pintype "passive"))
      (node (ref "C9") (pin "1") (pinfunction "1_1") (pintype "passive"))
      (node (ref "IC2") (pin "2") (pinfunction "OUT_2") (pintype "passive"))
      (node (ref "IC2") (pin "TAB") (pinfunction "OUT1_TAB") (pintype "passive"))
      (node (ref "IC4") (pin "P$15") (pinfunction "VDDTX_P$15") (pintype "input"))
      (node (ref "IC4") (pin "P$19") (pinfunction "VDDRX_P$19") (pintype "input"))
      (node (ref "IC4") (pin "P$20") (pinfunction "VDDPLL_P$20") (pintype "input"))
      (node (ref "IC4") (pin "P$25") (pinfunction "VDDOSC_P$25") (pintype "input"))
      (node (ref "IC4") (pin "P$28") (pinfunction "VDD_P$28") (pintype "input"))
      (node (ref "JP2") (pin "4") (pinfunction "4_4") (pintype "passive"))
      (node (ref "JP5") (pin "1") (pinfunction "1_1") (pintype "passive"))
      (node (ref "L3") (pin "1") (pinfunction "1_1") (pintype "passive"))
      (node (ref "R1") (pin "2") (pinfunction "2_2") (pintype "passive"))
      (node (ref "R10") (pin "2") (pinfunction "2_2") (pintype "passive"))
      (node (ref "R11") (pin "2") (pinfunction "2_2") (pintype "passive"))
      (node (ref "R13") (pin "2") (pinfunction "2_2") (pintype "passive"))
      (node (ref "R18") (pin "1") (pinfunction "1_1") (pintype "passive"))
      (node (ref "R34") (pin "2") (pinfunction "2_2") (pintype "passive"))
      (node (ref "R7") (pin "2") (pinfunction "2_2") (pintype "passive"))
      (node (ref "R8") (pin "2") (pinfunction "2_2") (pintype "passive"))
      (node (ref "R9") (pin "2") (pinfunction "2_2") (pintype "passive"))
      (node (ref "U$1") (pin "13") (pinfunction "VDD_13") (pintype "bidirectional"))
      (node (ref "U$1") (pin "23") (pinfunction "VUSB3V3_23") (pintype "bidirectional"))
      (node (ref "U$1") (pin "28") (pinfunction "AVDD_28") (pintype "bidirectional"))
      (node (ref "U$2") (pin "3") (pinfunction "~{WP}_3") (pintype "bidirectional"))
      (node (ref "U$2") (pin "7") (pinfunction "~{HOLD}_7") (pintype "bidirectional"))
      (node (ref "U$2") (pin "8") (pinfunction "VDD_8") (pintype "bidirectional"))
    )
    (net (code "63") (name "unconnected-(IC4-CLKOUT-PadP$3)") (class "Default")
      (node (ref "IC4") (pin "P$3") (pinfunction "CLKOUT_P$3") (pintype "output"))
    )
    (net (code "64") (name "unconnected-(IC4-NC*-PadP$5)") (class "Default")
      (node (ref "IC4") (pin "P$5") (pinfunction "NC*_P$5") (pintype "output"))
    )
    (net (code "65") (name "unconnected-(IC4-~{INT}-PadP$4)") (class "Default")
      (node (ref "IC4") (pin "P$4") (pinfunction "~{INT}_P$4") (pintype "output"))
    )
    (net (code "66") (name "unconnected-(JP1-Pad2)") (class "Default")
      (node (ref "JP1") (pin "2") (pinfunction "2_2") (pintype "passive"))
    )
    (net (code "67") (name "unconnected-(JP1-Pad6)") (class "Default")
      (node (ref "JP1") (pin "6") (pinfunction "6_6") (pintype "passive"))
    )
    (net (code "68") (name "unconnected-(JP4-D+-PadD+1)") (class "Default")
      (node (ref "JP4") (pin "D+1") (pinfunction "D+_D+1") (pintype "bidirectional"))
    )
    (net (code "69") (name "unconnected-(JP4-D--PadD-1)") (class "Default")
      (node (ref "JP4") (pin "D-1") (pinfunction "D-_D-1") (pintype "bidirectional"))
    )
    (net (code "70") (name "unconnected-(JP4-ID-PadID1)") (class "Default")
      (node (ref "JP4") (pin "ID1") (pinfunction "ID_ID1") (pintype "bidirectional"))
    )
    (net (code "71") (name "unconnected-(RJ1-PadNC)") (class "Default")
      (node (ref "RJ1") (pin "NC") (pinfunction "NC_NC") (pintype "bidirectional"))
    )
    (net (code "72") (name "unconnected-(RJ1-PadP5)") (class "Default")
      (node (ref "RJ1") (pin "P5") (pinfunction "P5_P5") (pintype "bidirectional"))
    )
  )
)
